# design.net
KiCad netlist of a schematic drawn in Altium Designer
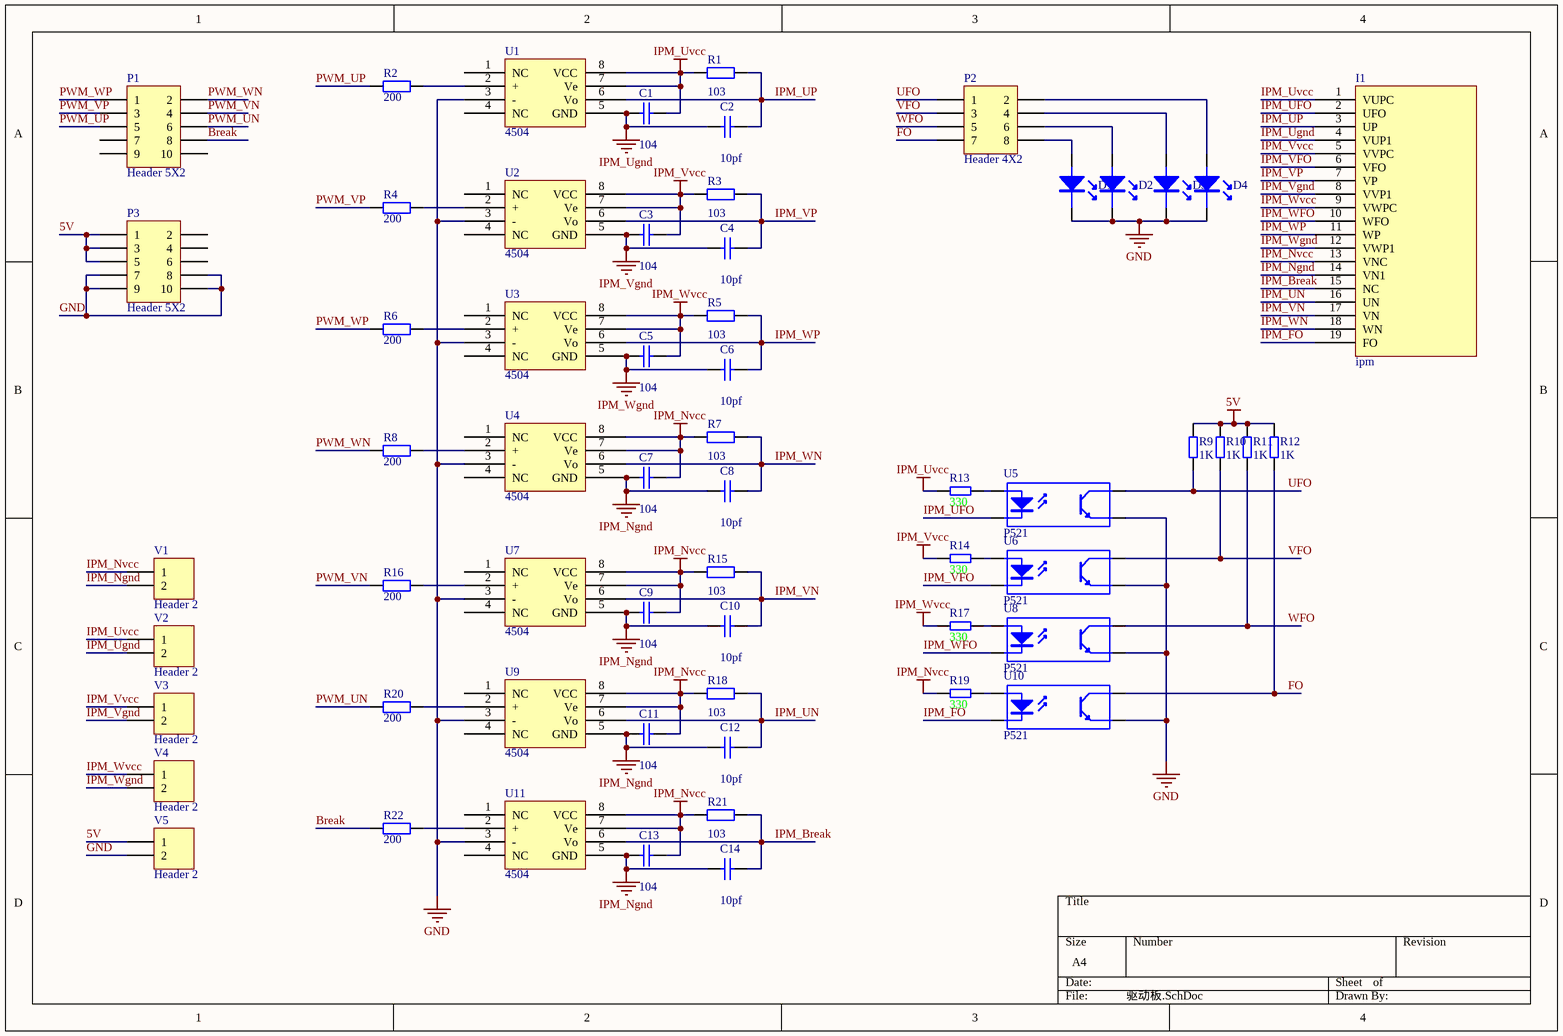
[diagram p0: 驱动板.SchDoc]

(export (version "E")
  (design (tool "Eeschema 10.0.6"))
  (components
    (comp (ref "C1")
      (value "104")
      (footprint "C0805")
      (description "Capacitor")
      (fields (field (name "Comment") "Cap") (field (name "PUBLISHER") "Altium Limited"))
      (libsource (lib "Miscellaneous Devices") (part "Cap"))
    )
    (comp (ref "C2")
      (value "10pf")
      (footprint "C0805")
      (description "Capacitor")
      (fields (field (name "Comment") "Cap") (field (name "PUBLISHER") "Altium Limited"))
      (libsource (lib "Miscellaneous Devices") (part "Cap"))
    )
    (comp (ref "C3")
      (value "104")
      (footprint "C0805")
      (description "Capacitor")
      (fields (field (name "Comment") "Cap") (field (name "PUBLISHER") "Altium Limited"))
      (libsource (lib "Miscellaneous Devices") (part "Cap"))
    )
    (comp (ref "C4")
      (value "10pf")
      (footprint "C0805")
      (description "Capacitor")
      (fields (field (name "Comment") "Cap") (field (name "PUBLISHER") "Altium Limited"))
      (libsource (lib "Miscellaneous Devices") (part "Cap"))
    )
    (comp (ref "C5")
      (value "104")
      (footprint "C0805")
      (description "Capacitor")
      (fields (field (name "Comment") "Cap") (field (name "PUBLISHER") "Altium Limited"))
      (libsource (lib "Miscellaneous Devices") (part "Cap"))
    )
    (comp (ref "C6")
      (value "10pf")
      (footprint "C0805")
      (description "Capacitor")
      (fields (field (name "Comment") "Cap") (field (name "PUBLISHER") "Altium Limited"))
      (libsource (lib "Miscellaneous Devices") (part "Cap"))
    )
    (comp (ref "C7")
      (value "104")
      (footprint "C0805")
      (description "Capacitor")
      (fields (field (name "Comment") "Cap") (field (name "PUBLISHER") "Altium Limited"))
      (libsource (lib "Miscellaneous Devices") (part "Cap"))
    )
    (comp (ref "C8")
      (value "10pf")
      (footprint "C0805")
      (description "Capacitor")
      (fields (field (name "Comment") "Cap") (field (name "PUBLISHER") "Altium Limited"))
      (libsource (lib "Miscellaneous Devices") (part "Cap"))
    )
    (comp (ref "C9")
      (value "104")
      (footprint "C0805")
      (description "Capacitor")
      (fields (field (name "Comment") "Cap") (field (name "PUBLISHER") "Altium Limited"))
      (libsource (lib "Miscellaneous Devices") (part "Cap"))
    )
    (comp (ref "C10")
      (value "10pf")
      (footprint "C0805")
      (description "Capacitor")
      (fields (field (name "Comment") "Cap") (field (name "PUBLISHER") "Altium Limited"))
      (libsource (lib "Miscellaneous Devices") (part "Cap"))
    )
    (comp (ref "C11")
      (value "104")
      (footprint "C0805")
      (description "Capacitor")
      (fields (field (name "Comment") "Cap") (field (name "PUBLISHER") "Altium Limited"))
      (libsource (lib "Miscellaneous Devices") (part "Cap"))
    )
    (comp (ref "C12")
      (value "10pf")
      (footprint "C0805")
      (description "Capacitor")
      (fields (field (name "Comment") "Cap") (field (name "PUBLISHER") "Altium Limited"))
      (libsource (lib "Miscellaneous Devices") (part "Cap"))
    )
    (comp (ref "C13")
      (value "104")
      (footprint "C0805")
      (description "Capacitor")
      (fields (field (name "Comment") "Cap") (field (name "PUBLISHER") "Altium Limited"))
      (libsource (lib "Miscellaneous Devices") (part "Cap"))
    )
    (comp (ref "C14")
      (value "10pf")
      (footprint "C0805")
      (description "Capacitor")
      (fields (field (name "Comment") "Cap") (field (name "PUBLISHER") "Altium Limited"))
      (libsource (lib "Miscellaneous Devices") (part "Cap"))
    )
    (comp (ref "D1") (value "LED") (footprint "3.2X1.6X1.1") (libsource (lib "CCDXPLIB") (part "LED")))
    (comp (ref "D2") (value "LED") (footprint "3.2X1.6X1.1") (libsource (lib "CCDXPLIB") (part "LED")))
    (comp (ref "D3") (value "LED") (footprint "3.2X1.6X1.1") (libsource (lib "CCDXPLIB") (part "LED")))
    (comp (ref "D4") (value "LED") (footprint "3.2X1.6X1.1") (libsource (lib "CCDXPLIB") (part "LED")))
    (comp (ref "I1") (value "ipm") (footprint "ipm") (libsource (lib "my schematic") (part "ipm")))
    (comp (ref "P1")
      (value "Header 5X2")
      (footprint "HDR2X5")
      (description "Header, 5-Pin, Dual row")
      (fields (field (name "PUBLISHER") "Altium Limited"))
      (libsource (lib "Miscellaneous Connectors") (part "Header 5X2"))
    )
    (comp (ref "P2")
      (value "Header 4X2")
      (footprint "HDR2X4")
      (description "Header, 4-Pin, Dual row")
      (fields (field (name "PUBLISHER") "Altium Limited"))
      (libsource (lib "Miscellaneous Connectors") (part "Header 4X2"))
    )
    (comp (ref "P3")
      (value "Header 5X2")
      (footprint "HDR2X5")
      (description "Header, 5-Pin, Dual row")
      (fields (field (name "PUBLISHER") "Altium Limited"))
      (libsource (lib "Miscellaneous Connectors") (part "Header 5X2"))
    )
    (comp (ref "R1")
      (value "103")
      (footprint "6-0805_N")
      (description "Resistor")
      (fields (field (name "Comment") "Res2") (field (name "PUBLISHER") "Altium Limited"))
      (libsource (lib "Miscellaneous Devices") (part "Res2"))
    )
    (comp (ref "R2")
      (value "200")
      (footprint "6-0805_N")
      (description "Resistor")
      (fields (field (name "Comment") "Res2") (field (name "PUBLISHER") "Altium Limited"))
      (libsource (lib "Miscellaneous Devices") (part "Res2"))
    )
    (comp (ref "R3")
      (value "103")
      (footprint "6-0805_N")
      (description "Resistor")
      (fields (field (name "Comment") "Res2") (field (name "PUBLISHER") "Altium Limited"))
      (libsource (lib "Miscellaneous Devices") (part "Res2"))
    )
    (comp (ref "R4")
      (value "200")
      (footprint "6-0805_N")
      (description "Resistor")
      (fields (field (name "Comment") "Res2") (field (name "PUBLISHER") "Altium Limited"))
      (libsource (lib "Miscellaneous Devices") (part "Res2"))
    )
    (comp (ref "R5")
      (value "103")
      (footprint "6-0805_N")
      (description "Resistor")
      (fields (field (name "Comment") "Res2") (field (name "PUBLISHER") "Altium Limited"))
      (libsource (lib "Miscellaneous Devices") (part "Res2"))
    )
    (comp (ref "R6")
      (value "200")
      (footprint "6-0805_N")
      (description "Resistor")
      (fields (field (name "Comment") "Res2") (field (name "PUBLISHER") "Altium Limited"))
      (libsource (lib "Miscellaneous Devices") (part "Res2"))
    )
    (comp (ref "R7")
      (value "103")
      (footprint "6-0805_N")
      (description "Resistor")
      (fields (field (name "Comment") "Res2") (field (name "PUBLISHER") "Altium Limited"))
      (libsource (lib "Miscellaneous Devices") (part "Res2"))
    )
    (comp (ref "R8")
      (value "200")
      (footprint "6-0805_N")
      (description "Resistor")
      (fields (field (name "Comment") "Res2") (field (name "PUBLISHER") "Altium Limited"))
      (libsource (lib "Miscellaneous Devices") (part "Res2"))
    )
    (comp (ref "R9")
      (value "1K")
      (footprint "6-0805_N")
      (description "电阻")
      (fields (field (name "Comment") "Res"))
      (libsource (lib "cloudlib") (part "Res"))
    )
    (comp (ref "R10")
      (value "1K")
      (footprint "6-0805_N")
      (description "电阻")
      (fields (field (name "Comment") "Res"))
      (libsource (lib "cloudlib") (part "Res"))
    )
    (comp (ref "R11")
      (value "1K")
      (footprint "6-0805_N")
      (description "电阻")
      (fields (field (name "Comment") "Res"))
      (libsource (lib "cloudlib") (part "Res"))
    )
    (comp (ref "R12")
      (value "1K")
      (footprint "6-0805_N")
      (description "电阻")
      (fields (field (name "Comment") "Res"))
      (libsource (lib "cloudlib") (part "Res"))
    )
    (comp (ref "R13")
      (value "330")
      (footprint "6-0805_N")
      (description "电阻")
      (fields (field (name "Comment") "Res Pack2"))
      (libsource (lib "cloudlib") (part "Res"))
    )
    (comp (ref "R14")
      (value "330")
      (footprint "6-0805_N")
      (description "电阻")
      (fields (field (name "Comment") "Res"))
      (libsource (lib "cloudlib") (part "Res"))
    )
    (comp (ref "R15")
      (value "103")
      (footprint "6-0805_N")
      (description "Resistor")
      (fields (field (name "Comment") "Res2") (field (name "PUBLISHER") "Altium Limited"))
      (libsource (lib "Miscellaneous Devices") (part "Res2"))
    )
    (comp (ref "R16")
      (value "200")
      (footprint "6-0805_N")
      (description "Resistor")
      (fields (field (name "Comment") "Res2") (field (name "PUBLISHER") "Altium Limited"))
      (libsource (lib "Miscellaneous Devices") (part "Res2"))
    )
    (comp (ref "R17")
      (value "330")
      (footprint "6-0805_N")
      (description "电阻")
      (fields (field (name "Comment") "Res"))
      (libsource (lib "cloudlib") (part "Res"))
    )
    (comp (ref "R18")
      (value "103")
      (footprint "6-0805_N")
      (description "Resistor")
      (fields (field (name "Comment") "Res2") (field (name "PUBLISHER") "Altium Limited"))
      (libsource (lib "Miscellaneous Devices") (part "Res2"))
    )
    (comp (ref "R19")
      (value "330")
      (footprint "6-0805_N")
      (description "电阻")
      (fields (field (name "Comment") "Res"))
      (libsource (lib "cloudlib") (part "Res"))
    )
    (comp (ref "R20")
      (value "200")
      (footprint "6-0805_N")
      (description "Resistor")
      (fields (field (name "Comment") "Res2") (field (name "PUBLISHER") "Altium Limited"))
      (libsource (lib "Miscellaneous Devices") (part "Res2"))
    )
    (comp (ref "R21")
      (value "103")
      (footprint "6-0805_N")
      (description "Resistor")
      (fields (field (name "Comment") "Res2") (field (name "PUBLISHER") "Altium Limited"))
      (libsource (lib "Miscellaneous Devices") (part "Res2"))
    )
    (comp (ref "R22")
      (value "200")
      (footprint "6-0805_N")
      (description "Resistor")
      (fields (field (name "Comment") "Res2") (field (name "PUBLISHER") "Altium Limited"))
      (libsource (lib "Miscellaneous Devices") (part "Res2"))
    )
    (comp (ref "U1") (value "4504") (footprint "DIP-8") (libsource (lib "my schematic") (part "4504")))
    (comp (ref "U2") (value "4504") (footprint "DIP-8") (libsource (lib "my schematic") (part "4504")))
    (comp (ref "U3") (value "4504") (footprint "DIP-8") (libsource (lib "my schematic") (part "4504")))
    (comp (ref "U4") (value "4504") (footprint "DIP-8") (libsource (lib "my schematic") (part "4504")))
    (comp (ref "U5")
      (value "P521")
      (footprint "DIP-4")
      (description "4-Pin Phototransistor Optocoupler")
      (fields (field (name "PUBLISHER") "Altium Limited"))
      (libsource (lib "Miscellaneous Devices") (part "Optoisolator1"))
    )
    (comp (ref "U6")
      (value "P521")
      (footprint "DIP-4")
      (description "4-Pin Phototransistor Optocoupler")
      (fields (field (name "PUBLISHER") "Altium Limited"))
      (libsource (lib "Miscellaneous Devices") (part "Optoisolator1"))
    )
    (comp (ref "U7") (value "4504") (footprint "DIP-8") (libsource (lib "my schematic") (part "4504")))
    (comp (ref "U8")
      (value "P521")
      (footprint "DIP-4")
      (description "4-Pin Phototransistor Optocoupler")
      (fields (field (name "PUBLISHER") "Altium Limited"))
      (libsource (lib "Miscellaneous Devices") (part "Optoisolator1"))
    )
    (comp (ref "U9") (value "4504") (footprint "DIP-8") (libsource (lib "my schematic") (part "4504")))
    (comp (ref "U10")
      (value "P521")
      (footprint "DIP-4")
      (description "4-Pin Phototransistor Optocoupler")
      (fields (field (name "PUBLISHER") "Altium Limited"))
      (libsource (lib "Miscellaneous Devices") (part "Optoisolator1"))
    )
    (comp (ref "U11") (value "4504") (footprint "DIP-8") (libsource (lib "my schematic") (part "4504")))
    (comp (ref "V1")
      (value "Header 2")
      (footprint "HDR1X2")
      (description "Header, 2-Pin")
      (fields (field (name "PUBLISHER") "Altium Limited"))
      (libsource (lib "Miscellaneous Connectors") (part "Header 2"))
    )
    (comp (ref "V2")
      (value "Header 2")
      (footprint "HDR1X2")
      (description "Header, 2-Pin")
      (fields (field (name "PUBLISHER") "Altium Limited"))
      (libsource (lib "Miscellaneous Connectors") (part "Header 2"))
    )
    (comp (ref "V3")
      (value "Header 2")
      (footprint "HDR1X2")
      (description "Header, 2-Pin")
      (fields (field (name "PUBLISHER") "Altium Limited"))
      (libsource (lib "Miscellaneous Connectors") (part "Header 2"))
    )
    (comp (ref "V4")
      (value "Header 2")
      (footprint "HDR1X2")
      (description "Header, 2-Pin")
      (fields (field (name "PUBLISHER") "Altium Limited"))
      (libsource (lib "Miscellaneous Connectors") (part "Header 2"))
    )
    (comp (ref "V5")
      (value "Header 2")
      (footprint "HDR1X2")
      (description "Header, 2-Pin")
      (fields (field (name "PUBLISHER") "Altium Limited"))
      (libsource (lib "Miscellaneous Connectors") (part "Header 2"))
    )
  )
  (nets
    (net (code "1") (name "/Break") (class "Default")
      (node (ref "P1") (pin "8") (pinfunction "8_8") (pintype "passive"))
      (node (ref "R22") (pin "1") (pinfunction "1_1") (pintype "passive"))
    )
    (net (code "2") (name "/FO") (class "Default")
      (node (ref "P2") (pin "7") (pinfunction "7_7") (pintype "passive"))
      (node (ref "R12") (pin "2") (pinfunction "2_2") (pintype "passive"))
      (node (ref "U10") (pin "4") (pinfunction "C_4") (pintype "passive"))
    )
    (net (code "3") (name "/IPM_Break") (class "Default")
      (node (ref "C14") (pin "2") (pinfunction "2_2") (pintype "passive"))
      (node (ref "I1") (pin "15") (pinfunction "NC_15") (pintype "passive"))
      (node (ref "R21") (pin "2") (pinfunction "2_2") (pintype "passive"))
      (node (ref "U11") (pin "6") (pinfunction "Vo_6") (pintype "passive"))
    )
    (net (code "4") (name "/IPM_FO") (class "Default")
      (node (ref "I1") (pin "19") (pinfunction "FO_19") (pintype "passive"))
      (node (ref "U10") (pin "2") (pinfunction "K_2") (pintype "passive"))
    )
    (net (code "5") (name "/IPM_UFO") (class "Default")
      (node (ref "I1") (pin "2") (pinfunction "UFO_2") (pintype "passive"))
      (node (ref "U5") (pin "2") (pinfunction "K_2") (pintype "passive"))
    )
    (net (code "6") (name "/IPM_UN") (class "Default")
      (node (ref "C12") (pin "2") (pinfunction "2_2") (pintype "passive"))
      (node (ref "I1") (pin "16") (pinfunction "UN_16") (pintype "passive"))
      (node (ref "R18") (pin "2") (pinfunction "2_2") (pintype "passive"))
      (node (ref "U9") (pin "6") (pinfunction "Vo_6") (pintype "passive"))
    )
    (net (code "7") (name "/IPM_UP") (class "Default")
      (node (ref "C2") (pin "2") (pinfunction "2_2") (pintype "passive"))
      (node (ref "I1") (pin "3") (pinfunction "UP_3") (pintype "passive"))
      (node (ref "R1") (pin "2") (pinfunction "2_2") (pintype "passive"))
      (node (ref "U1") (pin "6") (pinfunction "Vo_6") (pintype "passive"))
    )
    (net (code "8") (name "/IPM_VFO") (class "Default")
      (node (ref "I1") (pin "6") (pinfunction "VFO_6") (pintype "passive"))
      (node (ref "U6") (pin "2") (pinfunction "K_2") (pintype "passive"))
    )
    (net (code "9") (name "/IPM_VN") (class "Default")
      (node (ref "C10") (pin "2") (pinfunction "2_2") (pintype "passive"))
      (node (ref "I1") (pin "17") (pinfunction "VN_17") (pintype "passive"))
      (node (ref "R15") (pin "2") (pinfunction "2_2") (pintype "passive"))
      (node (ref "U7") (pin "6") (pinfunction "Vo_6") (pintype "passive"))
    )
    (net (code "10") (name "/IPM_VP") (class "Default")
      (node (ref "C4") (pin "2") (pinfunction "2_2") (pintype "passive"))
      (node (ref "I1") (pin "7") (pinfunction "VP_7") (pintype "passive"))
      (node (ref "R3") (pin "2") (pinfunction "2_2") (pintype "passive"))
      (node (ref "U2") (pin "6") (pinfunction "Vo_6") (pintype "passive"))
    )
    (net (code "11") (name "/IPM_WFO") (class "Default")
      (node (ref "I1") (pin "10") (pinfunction "WFO_10") (pintype "passive"))
      (node (ref "U8") (pin "2") (pinfunction "K_2") (pintype "passive"))
    )
    (net (code "12") (name "/IPM_WN") (class "Default")
      (node (ref "C8") (pin "2") (pinfunction "2_2") (pintype "passive"))
      (node (ref "I1") (pin "18") (pinfunction "WN_18") (pintype "passive"))
      (node (ref "R7") (pin "2") (pinfunction "2_2") (pintype "passive"))
      (node (ref "U4") (pin "6") (pinfunction "Vo_6") (pintype "passive"))
    )
    (net (code "13") (name "/IPM_WP") (class "Default")
      (node (ref "C6") (pin "2") (pinfunction "2_2") (pintype "passive"))
      (node (ref "I1") (pin "11") (pinfunction "WP_11") (pintype "passive"))
      (node (ref "R5") (pin "2") (pinfunction "2_2") (pintype "passive"))
      (node (ref "U3") (pin "6") (pinfunction "Vo_6") (pintype "passive"))
    )
    (net (code "14") (name "/PWM_UN") (class "Default")
      (node (ref "P1") (pin "6") (pinfunction "6_6") (pintype "passive"))
      (node (ref "R20") (pin "1") (pinfunction "1_1") (pintype "passive"))
    )
    (net (code "15") (name "/PWM_UP") (class "Default")
      (node (ref "P1") (pin "5") (pinfunction "5_5") (pintype "passive"))
      (node (ref "R2") (pin "1") (pinfunction "1_1") (pintype "passive"))
    )
    (net (code "16") (name "/PWM_VN") (class "Default")
      (node (ref "P1") (pin "4") (pinfunction "4_4") (pintype "passive"))
      (node (ref "R16") (pin "1") (pinfunction "1_1") (pintype "passive"))
    )
    (net (code "17") (name "/PWM_VP") (class "Default")
      (node (ref "P1") (pin "3") (pinfunction "3_3") (pintype "passive"))
      (node (ref "R4") (pin "1") (pinfunction "1_1") (pintype "passive"))
    )
    (net (code "18") (name "/PWM_WN") (class "Default")
      (node (ref "P1") (pin "2") (pinfunction "2_2") (pintype "passive"))
      (node (ref "R8") (pin "1") (pinfunction "1_1") (pintype "passive"))
    )
    (net (code "19") (name "/PWM_WP") (class "Default")
      (node (ref "P1") (pin "1") (pinfunction "1_1") (pintype "passive"))
      (node (ref "R6") (pin "1") (pinfunction "1_1") (pintype "passive"))
    )
    (net (code "20") (name "/UFO") (class "Default")
      (node (ref "P2") (pin "1") (pinfunction "1_1") (pintype "passive"))
      (node (ref "R9") (pin "2") (pinfunction "2_2") (pintype "passive"))
      (node (ref "U5") (pin "4") (pinfunction "C_4") (pintype "passive"))
    )
    (net (code "21") (name "/VFO") (class "Default")
      (node (ref "P2") (pin "3") (pinfunction "3_3") (pintype "passive"))
      (node (ref "R10") (pin "2") (pinfunction "2_2") (pintype "passive"))
      (node (ref "U6") (pin "4") (pinfunction "C_4") (pintype "passive"))
    )
    (net (code "22") (name "/WFO") (class "Default")
      (node (ref "P2") (pin "5") (pinfunction "5_5") (pintype "passive"))
      (node (ref "R11") (pin "2") (pinfunction "2_2") (pintype "passive"))
      (node (ref "U8") (pin "4") (pinfunction "C_4") (pintype "passive"))
    )
    (net (code "23") (name "5V") (class "Default")
      (node (ref "P3") (pin "1") (pinfunction "1_1") (pintype "passive"))
      (node (ref "P3") (pin "3") (pinfunction "3_3") (pintype "passive"))
      (node (ref "P3") (pin "5") (pinfunction "5_5") (pintype "passive"))
      (node (ref "R10") (pin "1") (pinfunction "1_1") (pintype "passive"))
      (node (ref "R11") (pin "1") (pinfunction "1_1") (pintype "passive"))
      (node (ref "R12") (pin "1") (pinfunction "1_1") (pintype "passive"))
      (node (ref "R9") (pin "1") (pinfunction "1_1") (pintype "passive"))
      (node (ref "V5") (pin "1") (pinfunction "1_1") (pintype "passive"))
    )
    (net (code "24") (name "GND") (class "Default")
      (node (ref "D1") (pin "2") (pinfunction "2_2") (pintype "passive"))
      (node (ref "D2") (pin "2") (pinfunction "2_2") (pintype "passive"))
      (node (ref "D3") (pin "2") (pinfunction "2_2") (pintype "passive"))
      (node (ref "D4") (pin "2") (pinfunction "2_2") (pintype "passive"))
      (node (ref "P3") (pin "10") (pinfunction "10_10") (pintype "passive"))
      (node (ref "P3") (pin "7") (pinfunction "7_7") (pintype "passive"))
      (node (ref "P3") (pin "8") (pinfunction "8_8") (pintype "passive"))
      (node (ref "P3") (pin "9") (pinfunction "9_9") (pintype "passive"))
      (node (ref "U1") (pin "3") (pinfunction "-_3") (pintype "passive"))
      (node (ref "U10") (pin "3") (pinfunction "E_3") (pintype "passive"))
      (node (ref "U11") (pin "3") (pinfunction "-_3") (pintype "passive"))
      (node (ref "U2") (pin "3") (pinfunction "-_3") (pintype "passive"))
      (node (ref "U3") (pin "3") (pinfunction "-_3") (pintype "passive"))
      (node (ref "U4") (pin "3") (pinfunction "-_3") (pintype "passive"))
      (node (ref "U5") (pin "3") (pinfunction "E_3") (pintype "passive"))
      (node (ref "U6") (pin "3") (pinfunction "E_3") (pintype "passive"))
      (node (ref "U7") (pin "3") (pinfunction "-_3") (pintype "passive"))
      (node (ref "U8") (pin "3") (pinfunction "E_3") (pintype "passive"))
      (node (ref "U9") (pin "3") (pinfunction "-_3") (pintype "passive"))
      (node (ref "V5") (pin "2") (pinfunction "2_2") (pintype "passive"))
    )
    (net (code "25") (name "IPM_Ngnd") (class "Default")
      (node (ref "C10") (pin "1") (pinfunction "1_1") (pintype "passive"))
      (node (ref "C11") (pin "1") (pinfunction "1_1") (pintype "passive"))
      (node (ref "C12") (pin "1") (pinfunction "1_1") (pintype "passive"))
      (node (ref "C13") (pin "1") (pinfunction "1_1") (pintype "passive"))
      (node (ref "C14") (pin "1") (pinfunction "1_1") (pintype "passive"))
      (node (ref "C7") (pin "1") (pinfunction "1_1") (pintype "passive"))
      (node (ref "C8") (pin "1") (pinfunction "1_1") (pintype "passive"))
      (node (ref "C9") (pin "1") (pinfunction "1_1") (pintype "passive"))
      (node (ref "I1") (pin "14") (pinfunction "VN1_14") (pintype "passive"))
      (node (ref "U11") (pin "5") (pinfunction "GND_5") (pintype "passive"))
      (node (ref "U4") (pin "5") (pinfunction "GND_5") (pintype "passive"))
      (node (ref "U7") (pin "5") (pinfunction "GND_5") (pintype "passive"))
      (node (ref "U9") (pin "5") (pinfunction "GND_5") (pintype "passive"))
      (node (ref "V1") (pin "2") (pinfunction "2_2") (pintype "passive"))
    )
    (net (code "26") (name "IPM_Nvcc") (class "Default")
      (node (ref "C11") (pin "2") (pinfunction "2_2") (pintype "passive"))
      (node (ref "C13") (pin "2") (pinfunction "2_2") (pintype "passive"))
      (node (ref "C7") (pin "2") (pinfunction "2_2") (pintype "passive"))
      (node (ref "C9") (pin "2") (pinfunction "2_2") (pintype "passive"))
      (node (ref "I1") (pin "13") (pinfunction "VNC_13") (pintype "passive"))
      (node (ref "R15") (pin "1") (pinfunction "1_1") (pintype "passive"))
      (node (ref "R18") (pin "1") (pinfunction "1_1") (pintype "passive"))
      (node (ref "R19") (pin "2") (pinfunction "2_2") (pintype "passive"))
      (node (ref "R21") (pin "1") (pinfunction "1_1") (pintype "passive"))
      (node (ref "R7") (pin "1") (pinfunction "1_1") (pintype "passive"))
      (node (ref "U11") (pin "7") (pinfunction "Ve_7") (pintype "passive"))
      (node (ref "U11") (pin "8") (pinfunction "VCC_8") (pintype "passive"))
      (node (ref "U4") (pin "7") (pinfunction "Ve_7") (pintype "passive"))
      (node (ref "U4") (pin "8") (pinfunction "VCC_8") (pintype "passive"))
      (node (ref "U7") (pin "7") (pinfunction "Ve_7") (pintype "passive"))
      (node (ref "U7") (pin "8") (pinfunction "VCC_8") (pintype "passive"))
      (node (ref "U9") (pin "7") (pinfunction "Ve_7") (pintype "passive"))
      (node (ref "U9") (pin "8") (pinfunction "VCC_8") (pintype "passive"))
      (node (ref "V1") (pin "1") (pinfunction "1_1") (pintype "passive"))
    )
    (net (code "27") (name "IPM_Ugnd") (class "Default")
      (node (ref "C1") (pin "1") (pinfunction "1_1") (pintype "passive"))
      (node (ref "C2") (pin "1") (pinfunction "1_1") (pintype "passive"))
      (node (ref "I1") (pin "4") (pinfunction "VUP1_4") (pintype "passive"))
      (node (ref "U1") (pin "5") (pinfunction "GND_5") (pintype "passive"))
      (node (ref "V2") (pin "2") (pinfunction "2_2") (pintype "passive"))
    )
    (net (code "28") (name "IPM_Uvcc") (class "Default")
      (node (ref "C1") (pin "2") (pinfunction "2_2") (pintype "passive"))
      (node (ref "I1") (pin "1") (pinfunction "VUPC_1") (pintype "passive"))
      (node (ref "R1") (pin "1") (pinfunction "1_1") (pintype "passive"))
      (node (ref "R13") (pin "2") (pinfunction "2_2") (pintype "passive"))
      (node (ref "U1") (pin "7") (pinfunction "Ve_7") (pintype "passive"))
      (node (ref "U1") (pin "8") (pinfunction "VCC_8") (pintype "passive"))
      (node (ref "V2") (pin "1") (pinfunction "1_1") (pintype "passive"))
    )
    (net (code "29") (name "IPM_Vgnd") (class "Default")
      (node (ref "C3") (pin "1") (pinfunction "1_1") (pintype "passive"))
      (node (ref "C4") (pin "1") (pinfunction "1_1") (pintype "passive"))
      (node (ref "I1") (pin "8") (pinfunction "VVP1_8") (pintype "passive"))
      (node (ref "U2") (pin "5") (pinfunction "GND_5") (pintype "passive"))
      (node (ref "V3") (pin "2") (pinfunction "2_2") (pintype "passive"))
    )
    (net (code "30") (name "IPM_Vvcc") (class "Default")
      (node (ref "C3") (pin "2") (pinfunction "2_2") (pintype "passive"))
      (node (ref "I1") (pin "5") (pinfunction "VVPC_5") (pintype "passive"))
      (node (ref "R14") (pin "2") (pinfunction "2_2") (pintype "passive"))
      (node (ref "R3") (pin "1") (pinfunction "1_1") (pintype "passive"))
      (node (ref "U2") (pin "7") (pinfunction "Ve_7") (pintype "passive"))
      (node (ref "U2") (pin "8") (pinfunction "VCC_8") (pintype "passive"))
      (node (ref "V3") (pin "1") (pinfunction "1_1") (pintype "passive"))
    )
    (net (code "31") (name "IPM_Wgnd") (class "Default")
      (node (ref "C5") (pin "1") (pinfunction "1_1") (pintype "passive"))
      (node (ref "C6") (pin "1") (pinfunction "1_1") (pintype "passive"))
      (node (ref "I1") (pin "12") (pinfunction "VWP1_12") (pintype "passive"))
      (node (ref "U3") (pin "5") (pinfunction "GND_5") (pintype "passive"))
      (node (ref "V4") (pin "2") (pinfunction "2_2") (pintype "passive"))
    )
    (net (code "32") (name "IPM_Wvcc") (class "Default")
      (node (ref "C5") (pin "2") (pinfunction "2_2") (pintype "passive"))
      (node (ref "I1") (pin "9") (pinfunction "VWPC_9") (pintype "passive"))
      (node (ref "R17") (pin "2") (pinfunction "2_2") (pintype "passive"))
      (node (ref "R5") (pin "1") (pinfunction "1_1") (pintype "passive"))
      (node (ref "U3") (pin "7") (pinfunction "Ve_7") (pintype "passive"))
      (node (ref "U3") (pin "8") (pinfunction "VCC_8") (pintype "passive"))
      (node (ref "V4") (pin "1") (pinfunction "1_1") (pintype "passive"))
    )
    (net (code "33") (name "Net-(D1-Pad1)") (class "Default")
      (node (ref "D1") (pin "1") (pinfunction "1_1") (pintype "passive"))
      (node (ref "P2") (pin "8") (pinfunction "8_8") (pintype "passive"))
    )
    (net (code "34") (name "Net-(D2-Pad1)") (class "Default")
      (node (ref "D2") (pin "1") (pinfunction "1_1") (pintype "passive"))
      (node (ref "P2") (pin "6") (pinfunction "6_6") (pintype "passive"))
    )
    (net (code "35") (name "Net-(D3-Pad1)") (class "Default")
      (node (ref "D3") (pin "1") (pinfunction "1_1") (pintype "passive"))
      (node (ref "P2") (pin "4") (pinfunction "4_4") (pintype "passive"))
    )
    (net (code "36") (name "Net-(D4-Pad1)") (class "Default")
      (node (ref "D4") (pin "1") (pinfunction "1_1") (pintype "passive"))
      (node (ref "P2") (pin "2") (pinfunction "2_2") (pintype "passive"))
    )
    (net (code "37") (name "Net-(U1-+)") (class "Default")
      (node (ref "R2") (pin "2") (pinfunction "2_2") (pintype "passive"))
      (node (ref "U1") (pin "2") (pinfunction "+_2") (pintype "passive"))
    )
    (net (code "38") (name "Net-(U2-+)") (class "Default")
      (node (ref "R4") (pin "2") (pinfunction "2_2") (pintype "passive"))
      (node (ref "U2") (pin "2") (pinfunction "+_2") (pintype "passive"))
    )
    (net (code "39") (name "Net-(U3-+)") (class "Default")
      (node (ref "R6") (pin "2") (pinfunction "2_2") (pintype "passive"))
      (node (ref "U3") (pin "2") (pinfunction "+_2") (pintype "passive"))
    )
    (net (code "40") (name "Net-(U4-+)") (class "Default")
      (node (ref "R8") (pin "2") (pinfunction "2_2") (pintype "passive"))
      (node (ref "U4") (pin "2") (pinfunction "+_2") (pintype "passive"))
    )
    (net (code "41") (name "Net-(U5-A)") (class "Default")
      (node (ref "R13") (pin "1") (pinfunction "1_1") (pintype "passive"))
      (node (ref "U5") (pin "1") (pinfunction "A_1") (pintype "passive"))
    )
    (net (code "42") (name "Net-(U6-A)") (class "Default")
      (node (ref "R14") (pin "1") (pinfunction "1_1") (pintype "passive"))
      (node (ref "U6") (pin "1") (pinfunction "A_1") (pintype "passive"))
    )
    (net (code "43") (name "Net-(U7-+)") (class "Default")
      (node (ref "R16") (pin "2") (pinfunction "2_2") (pintype "passive"))
      (node (ref "U7") (pin "2") (pinfunction "+_2") (pintype "passive"))
    )
    (net (code "44") (name "Net-(U8-A)") (class "Default")
      (node (ref "R17") (pin "1") (pinfunction "1_1") (pintype "passive"))
      (node (ref "U8") (pin "1") (pinfunction "A_1") (pintype "passive"))
    )
    (net (code "45") (name "Net-(U9-+)") (class "Default")
      (node (ref "R20") (pin "2") (pinfunction "2_2") (pintype "passive"))
      (node (ref "U9") (pin "2") (pinfunction "+_2") (pintype "passive"))
    )
    (net (code "46") (name "Net-(U10-A)") (class "Default")
      (node (ref "R19") (pin "1") (pinfunction "1_1") (pintype "passive"))
      (node (ref "U10") (pin "1") (pinfunction "A_1") (pintype "passive"))
    )
    (net (code "47") (name "Net-(U11-+)") (class "Default")
      (node (ref "R22") (pin "2") (pinfunction "2_2") (pintype "passive"))
      (node (ref "U11") (pin "2") (pinfunction "+_2") (pintype "passive"))
    )
    (net (code "48") (name "unconnected-(P1-Pad7)") (class "Default")
      (node (ref "P1") (pin "7") (pinfunction "7_7") (pintype "passive"))
    )
    (net (code "49") (name "unconnected-(P1-Pad9)") (class "Default")
      (node (ref "P1") (pin "9") (pinfunction "9_9") (pintype "passive"))
    )
    (net (code "50") (name "unconnected-(P1-Pad10)") (class "Default")
      (node (ref "P1") (pin "10") (pinfunction "10_10") (pintype "passive"))
    )
    (net (code "51") (name "unconnected-(P3-Pad2)") (class "Default")
      (node (ref "P3") (pin "2") (pinfunction "2_2") (pintype "passive"))
    )
    (net (code "52") (name "unconnected-(P3-Pad4)") (class "Default")
      (node (ref "P3") (pin "4") (pinfunction "4_4") (pintype "passive"))
    )
    (net (code "53") (name "unconnected-(P3-Pad6)") (class "Default")
      (node (ref "P3") (pin "6") (pinfunction "6_6") (pintype "passive"))
    )
    (net (code "54") (name "unconnected-(U1-NC-Pad1)") (class "Default")
      (node (ref "U1") (pin "1") (pinfunction "NC_1") (pintype "passive"))
    )
    (net (code "55") (name "unconnected-(U1-NC-Pad4)") (class "Default")
      (node (ref "U1") (pin "4") (pinfunction "NC_4") (pintype "passive"))
    )
    (net (code "56") (name "unconnected-(U2-NC-Pad1)") (class "Default")
      (node (ref "U2") (pin "1") (pinfunction "NC_1") (pintype "passive"))
    )
    (net (code "57") (name "unconnected-(U2-NC-Pad4)") (class "Default")
      (node (ref "U2") (pin "4") (pinfunction "NC_4") (pintype "passive"))
    )
    (net (code "58") (name "unconnected-(U3-NC-Pad1)") (class "Default")
      (node (ref "U3") (pin "1") (pinfunction "NC_1") (pintype "passive"))
    )
    (net (code "59") (name "unconnected-(U3-NC-Pad4)") (class "Default")
      (node (ref "U3") (pin "4") (pinfunction "NC_4") (pintype "passive"))
    )
    (net (code "60") (name "unconnected-(U4-NC-Pad1)") (class "Default")
      (node (ref "U4") (pin "1") (pinfunction "NC_1") (pintype "passive"))
    )
    (net (code "61") (name "unconnected-(U4-NC-Pad4)") (class "Default")
      (node (ref "U4") (pin "4") (pinfunction "NC_4") (pintype "passive"))
    )
    (net (code "62") (name "unconnected-(U7-NC-Pad1)") (class "Default")
      (node (ref "U7") (pin "1") (pinfunction "NC_1") (pintype "passive"))
    )
    (net (code "63") (name "unconnected-(U7-NC-Pad4)") (class "Default")
      (node (ref "U7") (pin "4") (pinfunction "NC_4") (pintype "passive"))
    )
    (net (code "64") (name "unconnected-(U9-NC-Pad1)") (class "Default")
      (node (ref "U9") (pin "1") (pinfunction "NC_1") (pintype "passive"))
    )
    (net (code "65") (name "unconnected-(U9-NC-Pad4)") (class "Default")
      (node (ref "U9") (pin "4") (pinfunction "NC_4") (pintype "passive"))
    )
    (net (code "66") (name "unconnected-(U11-NC-Pad1)") (class "Default")
      (node (ref "U11") (pin "1") (pinfunction "NC_1") (pintype "passive"))
    )
    (net (code "67") (name "unconnected-(U11-NC-Pad4)") (class "Default")
      (node (ref "U11") (pin "4") (pinfunction "NC_4") (pintype "passive"))
    )
  )
)
